# POWER.net
KiCad netlist of a schematic drawn in Altium Designer
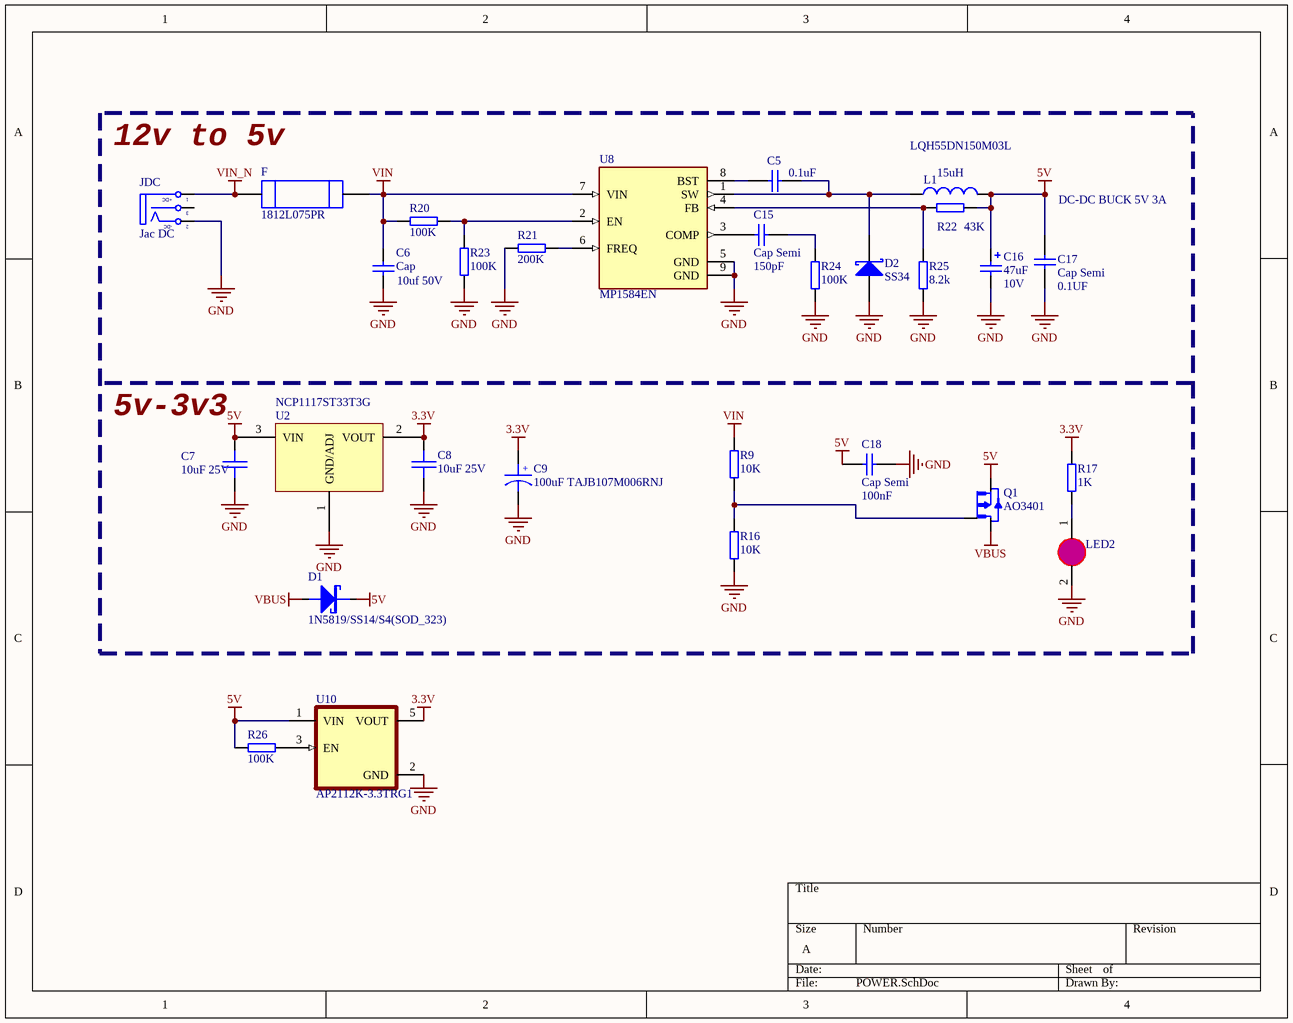
[diagram p0: POWER.SchDoc]

(export (version "E")
  (design (tool "Eeschema 10.0.6"))
  (components
    (comp (ref "C5")
      (value "0.1uF")
      (footprint "SMT0603")
      (description "CAP SM 0603 X5R 10uF 10%")
      (fields (field (name "TOLERANCE") "±10%") (field (name "Comment") "Cap Semi"))
      (libsource (lib "electronpowered") (part "CAP-SM-0603-X5R-10uF"))
    )
    (comp (ref "C6")
      (value "Cap")
      (footprint "1206")
      (description "Capacitor")
      (fields (field (name "ALTIUM_VALUE") "10uf 50V") (field (name "PUBLISHER") "Altium Limited"))
      (libsource (lib "Miscellaneous Devices") (part "Cap"))
    )
    (comp (ref "C7")
      (value "10uF 25V")
      (footprint "SMT_C_0805")
      (description "Surface mount capacitor 0805")
      (libsource (lib "NODEMCU_DEVKIT_V1.0") (part "SMT_C_0805"))
    )
    (comp (ref "C8")
      (value "10uF 25V")
      (footprint "SMT_C_0805")
      (description "Surface mount capacitor 0805")
      (libsource (lib "NODEMCU_DEVKIT_V1.0") (part "SMT_C_0805"))
    )
    (comp (ref "C9")
      (value "100uF TAJB107M006RNJ")
      (footprint "SMT_C_Tantalum_B")
      (description "Capacitor, SM Tantalum; Body 3.5 x 2.8 mm (LxW typ)")
      (libsource (lib "NODEMCU_DEVKIT_V1.0") (part "SMT_C_Tantalum_B"))
    )
    (comp (ref "C15")
      (value "Cap Semi")
      (footprint "SMT0603")
      (description "CAP SM 0603 X5R 10uF 10%")
      (fields (field (name "TOLERANCE") "±10%") (field (name "ALTIUM_VALUE") "150pF"))
      (libsource (lib "electronpowered") (part "CAP-SM-0603-X5R-10uF"))
    )
    (comp (ref "C16")
      (value "47uF")
      (footprint "Tantal_B")
      (description "Polarized Capacitor (Axial)")
      (fields (field (name "VOLTAGE") "10V") (field (name "PUBLISHER") "Altium Limited"))
      (libsource (lib "mp1584") (part "Cap Pol"))
    )
    (comp (ref "C17")
      (value "Cap Semi")
      (footprint "SMT0603")
      (description "CAP SM 0603 X5R 10uF 10%")
      (fields (field (name "TOLERANCE") "±10%") (field (name "ALTIUM_VALUE") "0.1UF"))
      (libsource (lib "electronpowered") (part "CAP-SM-0603-X5R-10uF"))
    )
    (comp (ref "C18")
      (value "Cap Semi")
      (footprint "SMT0603")
      (description "CAP SM 0603 X7R 100nF 10%")
      (fields (field (name "TOLERANCE") "±10%") (field (name "ALTIUM_VALUE") "100nF"))
      (libsource (lib "electronpowered") (part "CAP-SM-0603-X7R-100nF"))
    )
    (comp (ref "D1")
      (value "1N5819/SS14/S4(SOD_323)")
      (footprint "SMT_DIODE_SOD_323")
      (description "Surface mount schottky diode SOD-323(0805) Package")
      (libsource (lib "NODEMCU_DEVKIT_V1.0") (part "SMT_DIODE_SCHOTTKY_SOD_323"))
    )
    (comp (ref "D2")
      (value "SS34")
      (footprint "SMB")
      (description "Schottky Diode")
      (fields (field (name "PUBLISHER") "Altium Limited"))
      (libsource (lib "mp1584") (part "D Schottky"))
    )
    (comp (ref "F")
      (value "1812L075PR")
      (footprint "1812")
      (description "Polymeric PTC Resettable Fuse 13.2V 750mA Ih Surface Mount 1812 _4532 Metric_, Concave")
      (fields (field (name "MF") "Littelfuse Inc."))
      (libsource (lib "1812L075PR") (part "1812L075PR"))
    )
    (comp (ref "JDC")
      (value "Jac DC")
      (footprint "DC-IN")
      (description "Jac DC input")
      (libsource (lib "My Library") (part "DCIN"))
    )
    (comp (ref "L1")
      (value "15uH")
      (footprint "Inductor SMD 6.8*6.8*4.5")
      (fields (field (name "MARKA") "LQH55DN150M03L"))
      (libsource (lib "mp1584") (part "Inductor"))
    )
    (comp (ref "LED2")
      (value "LED3")
      (footprint "LED0805")
      (description "LED SMD 0805")
      (libsource (lib "My Library") (part "LED0805"))
    )
    (comp (ref "Q1")
      (value "AO3401")
      (footprint "SOT23")
      (description "P-Channel 30V 4A _Ta_ 1.4W _Ta_ Surface Mount SOT-23-3")
      (fields (field (name "MF") "Alpha & Omega Semiconductor"))
      (libsource (lib "AO3401") (part "AO3401"))
    )
    (comp (ref "R9")
      (value "10K")
      (footprint "SMT0603")
      (description "RES SM 0603 10K")
      (fields (field (name "Comment") "Resistor"))
      (libsource (lib "electronpowered") (part "RES-SM-0603-10K"))
    )
    (comp (ref "R16")
      (value "10K")
      (footprint "SMT0603")
      (description "RES SM 0603 10K")
      (fields (field (name "Comment") "Resistor"))
      (libsource (lib "electronpowered") (part "RES-SM-0603-10K"))
    )
    (comp (ref "R17")
      (value "1K")
      (footprint "SMT0603")
      (description "RES SM 0603 100K")
      (fields (field (name "Comment") "Resistor"))
      (libsource (lib "electronpowered") (part "RES-SM-0603-100K"))
    )
    (comp (ref "R20")
      (value "100K")
      (footprint "SMT0603")
      (description "RES SM 0603 100K")
      (fields (field (name "Comment") "Resistor"))
      (libsource (lib "electronpowered") (part "RES-SM-0603-100K"))
    )
    (comp (ref "R21")
      (value "200K")
      (footprint "SMT0603")
      (description "RES SM 0603 100K")
      (fields (field (name "Comment") "Resistor"))
      (libsource (lib "electronpowered") (part "RES-SM-0603-100K"))
    )
    (comp (ref "R22")
      (value "43K")
      (footprint "SMT0603")
      (description "RES SM 0603 100K")
      (fields (field (name "Comment") "Resistor"))
      (libsource (lib "electronpowered") (part "RES-SM-0603-100K"))
    )
    (comp (ref "R23")
      (value "100K")
      (footprint "SMT0603")
      (description "RES SM 0603 100K")
      (fields (field (name "Comment") "Resistor"))
      (libsource (lib "electronpowered") (part "RES-SM-0603-100K"))
    )
    (comp (ref "R24")
      (value "100K")
      (footprint "SMT0603")
      (description "RES SM 0603 100K")
      (fields (field (name "Comment") "Resistor"))
      (libsource (lib "electronpowered") (part "RES-SM-0603-100K"))
    )
    (comp (ref "R25")
      (value "8.2k")
      (footprint "SMT0603")
      (description "RES SM 0603 100K")
      (fields (field (name "Comment") "Resistor"))
      (libsource (lib "electronpowered") (part "RES-SM-0603-100K"))
    )
    (comp (ref "R26")
      (value "100K")
      (footprint "SMT0603")
      (description "RES SM 0603 100K")
      (fields (field (name "Comment") "Resistor"))
      (libsource (lib "electronpowered") (part "RES-SM-0603-100K"))
    )
    (comp (ref "U2")
      (value "NCP1117ST33T3G")
      (footprint "SOT-223")
      (description "NCP1117, NCV1117. 1.0 A Low-Dropout Positive  Fixed and Adjustable  Voltage Regulators")
      (libsource (lib "NODEMCU_DEVKIT_V1.0") (part "NCP1117"))
    )
    (comp (ref "U8")
      (value "MP1584EN")
      (footprint "SOIC127P600X170-9N")
      (fields (field (name "MF") "Monolithic Power"))
      (libsource (lib "MP1584EN") (part "MP1584EN"))
    )
    (comp (ref "U10")
      (value "AP2112K-3.3TRG1")
      (footprint "SOT95P285X140-5N")
      (description "Linear Voltage Regulator IC 1 Output 600mA SOT-25")
      (fields
        (field (name "DIGI-KEY_PART_NUMBER") "AP2112K-3.3TRG1DICT-ND")
        (field (name "MF") "Diodes Inc.")
      )
      (libsource (lib "AP2112K-3.3TRG1") (part "AP2112K-3.3TRG1"))
    )
  )
  (nets
    (net (code "1") (name "3.3V") (class "Default")
      (node (ref "C8") (pin "1") (pinfunction "1_1") (pintype "passive"))
      (node (ref "C9") (pin "1") (pinfunction "1_1") (pintype "passive"))
      (node (ref "R17") (pin "1") (pinfunction "1_1") (pintype "passive"))
      (node (ref "U10") (pin "5") (pinfunction "VOUT_5") (pintype "power_in"))
      (node (ref "U2") (pin "2") (pinfunction "VOUT_2") (pintype "passive"))
    )
    (net (code "2") (name "5V") (class "Default")
      (node (ref "C16") (pin "1") (pinfunction "1_1") (pintype "passive"))
      (node (ref "C17") (pin "1") (pinfunction "1_1") (pintype "passive"))
      (node (ref "C18") (pin "1") (pinfunction "1_1") (pintype "passive"))
      (node (ref "C7") (pin "1") (pinfunction "1_1") (pintype "passive"))
      (node (ref "D1") (pin "2") (pinfunction "K_2") (pintype "passive"))
      (node (ref "L1") (pin "2") (pinfunction "2_2") (pintype "passive"))
      (node (ref "Q1") (pin "2") (pinfunction "S_2") (pintype "passive"))
      (node (ref "R22") (pin "1") (pinfunction "1_1") (pintype "passive"))
      (node (ref "R26") (pin "2") (pinfunction "2_2") (pintype "passive"))
      (node (ref "U10") (pin "1") (pinfunction "VIN_1") (pintype "power_in"))
      (node (ref "U2") (pin "3") (pinfunction "VIN_3") (pintype "passive"))
    )
    (net (code "3") (name "GND") (class "Default")
      (node (ref "C16") (pin "2") (pinfunction "2_2") (pintype "passive"))
      (node (ref "C17") (pin "2") (pinfunction "2_2") (pintype "passive"))
      (node (ref "C18") (pin "2") (pinfunction "2_2") (pintype "passive"))
      (node (ref "C6") (pin "2") (pinfunction "2_2") (pintype "passive"))
      (node (ref "C7") (pin "2") (pinfunction "2_2") (pintype "passive"))
      (node (ref "C8") (pin "2") (pinfunction "2_2") (pintype "passive"))
      (node (ref "C9") (pin "2") (pinfunction "2_2") (pintype "passive"))
      (node (ref "D2") (pin "1") (pinfunction "A_1") (pintype "passive"))
      (node (ref "JDC") (pin "2") (pinfunction "TN_2") (pintype "passive"))
      (node (ref "LED2") (pin "2") (pinfunction "K_2") (pintype "passive"))
      (node (ref "R16") (pin "1") (pinfunction "1_1") (pintype "passive"))
      (node (ref "R21") (pin "1") (pinfunction "1_1") (pintype "passive"))
      (node (ref "R23") (pin "2") (pinfunction "2_2") (pintype "passive"))
      (node (ref "R24") (pin "1") (pinfunction "1_1") (pintype "passive"))
      (node (ref "R25") (pin "2") (pinfunction "2_2") (pintype "passive"))
      (node (ref "U10") (pin "2") (pinfunction "GND_2") (pintype "power_in"))
      (node (ref "U2") (pin "1") (pinfunction "GND/ADJ_1") (pintype "passive"))
      (node (ref "U8") (pin "5") (pinfunction "GND_5") (pintype "power_in"))
      (node (ref "U8") (pin "9") (pinfunction "GND_9") (pintype "power_in"))
    )
    (net (code "4") (name "Net-(C15-Pad1)") (class "Default")
      (node (ref "C15") (pin "1") (pinfunction "1_1") (pintype "passive"))
      (node (ref "R24") (pin "2") (pinfunction "2_2") (pintype "passive"))
    )
    (net (code "5") (name "Net-(D2-K)") (class "Default")
      (node (ref "C5") (pin "1") (pinfunction "1_1") (pintype "passive"))
      (node (ref "D2") (pin "2") (pinfunction "K_2") (pintype "passive"))
      (node (ref "L1") (pin "1") (pinfunction "1_1") (pintype "passive"))
      (node (ref "U8") (pin "1") (pinfunction "SW_1") (pintype "output"))
    )
    (net (code "6") (name "Net-(LED2-A)") (class "Default")
      (node (ref "LED2") (pin "1") (pinfunction "A_1") (pintype "passive"))
      (node (ref "R17") (pin "2") (pinfunction "2_2") (pintype "passive"))
    )
    (net (code "7") (name "Net-(Q1-G)") (class "Default")
      (node (ref "Q1") (pin "1") (pinfunction "G_1") (pintype "passive"))
      (node (ref "R16") (pin "2") (pinfunction "2_2") (pintype "passive"))
      (node (ref "R9") (pin "1") (pinfunction "1_1") (pintype "passive"))
    )
    (net (code "8") (name "Net-(U8-BST)") (class "Default")
      (node (ref "C5") (pin "2") (pinfunction "2_2") (pintype "passive"))
      (node (ref "U8") (pin "8") (pinfunction "BST_8") (pintype "passive"))
    )
    (net (code "9") (name "Net-(U8-COMP)") (class "Default")
      (node (ref "C15") (pin "2") (pinfunction "2_2") (pintype "passive"))
      (node (ref "U8") (pin "3") (pinfunction "COMP_3") (pintype "output"))
    )
    (net (code "10") (name "Net-(U8-EN)") (class "Default")
      (node (ref "R20") (pin "2") (pinfunction "2_2") (pintype "passive"))
      (node (ref "R23") (pin "1") (pinfunction "1_1") (pintype "passive"))
      (node (ref "U8") (pin "2") (pinfunction "EN_2") (pintype "input"))
    )
    (net (code "11") (name "Net-(U8-FB)") (class "Default")
      (node (ref "R22") (pin "2") (pinfunction "2_2") (pintype "passive"))
      (node (ref "R25") (pin "1") (pinfunction "1_1") (pintype "passive"))
      (node (ref "U8") (pin "4") (pinfunction "FB_4") (pintype "input"))
    )
    (net (code "12") (name "Net-(U8-FREQ)") (class "Default")
      (node (ref "R21") (pin "2") (pinfunction "2_2") (pintype "passive"))
      (node (ref "U8") (pin "6") (pinfunction "FREQ_6") (pintype "input"))
    )
    (net (code "13") (name "Net-(U10-EN)") (class "Default")
      (node (ref "R26") (pin "1") (pinfunction "1_1") (pintype "passive"))
      (node (ref "U10") (pin "3") (pinfunction "EN_3") (pintype "input"))
    )
    (net (code "14") (name "VBUS") (class "Default")
      (node (ref "D1") (pin "1") (pinfunction "A_1") (pintype "passive"))
      (node (ref "Q1") (pin "3") (pinfunction "D_3") (pintype "passive"))
    )
    (net (code "15") (name "VIN") (class "Default")
      (node (ref "C6") (pin "1") (pinfunction "1_1") (pintype "passive"))
      (node (ref "F") (pin "2") (pinfunction "2_2") (pintype "passive"))
      (node (ref "R20") (pin "1") (pinfunction "1_1") (pintype "passive"))
      (node (ref "R9") (pin "2") (pinfunction "2_2") (pintype "passive"))
      (node (ref "U8") (pin "7") (pinfunction "VIN_7") (pintype "input"))
    )
    (net (code "16") (name "VIN_N") (class "Default")
      (node (ref "F") (pin "1") (pinfunction "1_1") (pintype "passive"))
      (node (ref "JDC") (pin "1") (pinfunction "T_1") (pintype "passive"))
    )
    (net (code "17") (name "unconnected-(JDC-S-Pad3)") (class "Default")
      (node (ref "JDC") (pin "3") (pinfunction "S_3") (pintype "power_in"))
    )
  )
)
